# aasdasd.net
KiCad netlist of a schematic drawn in EAGLE
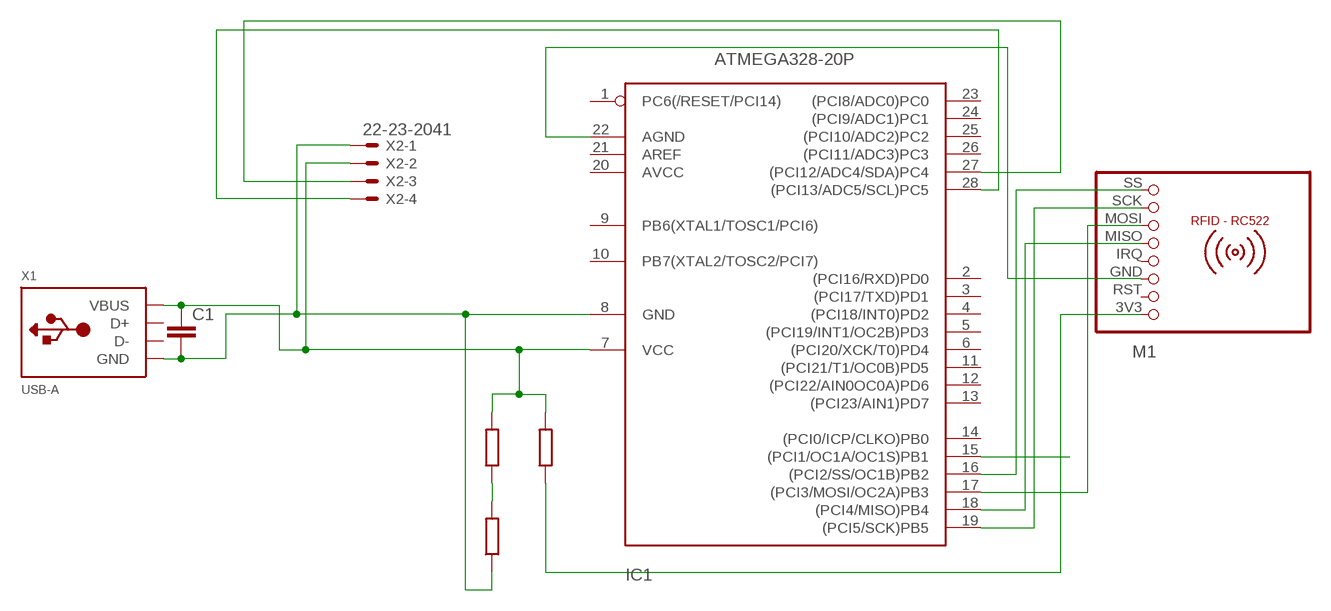
[diagram p0: schematic, sheet 1]

(export (version "E")
  (design (tool "Eeschema 10.0.6"))
  (components
    (comp (ref "C1")
      (value "C-EU025-050X050")
      (footprint "eagle-import:C025-050X050")
      (libsource (lib "eagle-import") (part "C-EU025-050X050"))
    )
    (comp (ref "IC1")
      (value "ATMEGA328-20P")
      (footprint "eagle-import:DIL28-3")
      (libsource (lib "eagle-import") (part "ATMEGA328P-20"))
    )
    (comp (ref "M1")
      (value "RFID-RC522")
      (footprint "eagle-import:RFID-RC522")
      (libsource (lib "eagle-import") (part "RFID-RC522"))
    )
    (comp (ref "X1")
      (value "USB-A")
      (footprint "eagle-import:MOLEX_480371000")
      (libsource (lib "eagle-import") (part "USB-A"))
    )
    (comp (ref "X2")
      (value "22-23-2041")
      (footprint "eagle-import:22-23-2041")
      (fields (field (name "MF") "MOLEX"))
      (libsource (lib "eagle-import") (part "22-23-2041"))
    )
  )
  (nets
    (net (code "1") (name "Net-(IC1-(PCI2{slash}SS{slash}OC1B)PB2)") (class "Default")
      (node (ref "IC1") (pin "16") (pinfunction "(PCI2/SS/OC1B)PB2_16") (pintype "bidirectional"))
      (node (ref "M1") (pin "SS") (pinfunction "8_SS") (pintype "passive"))
    )
    (net (code "2") (name "Net-(IC1-(PCI3{slash}MOSI{slash}OC2A)PB3)") (class "Default")
      (node (ref "IC1") (pin "17") (pinfunction "(PCI3/MOSI/OC2A)PB3_17") (pintype "bidirectional"))
      (node (ref "M1") (pin "MOSI") (pinfunction "6_MOSI") (pintype "passive"))
    )
    (net (code "3") (name "Net-(IC1-(PCI4{slash}MISO)PB4)") (class "Default")
      (node (ref "IC1") (pin "18") (pinfunction "(PCI4/MISO)PB4_18") (pintype "bidirectional"))
      (node (ref "M1") (pin "MISO") (pinfunction "5_MISO") (pintype "passive"))
    )
    (net (code "4") (name "Net-(IC1-(PCI5{slash}SCK)PB5)") (class "Default")
      (node (ref "IC1") (pin "19") (pinfunction "(PCI5/SCK)PB5_19") (pintype "bidirectional"))
      (node (ref "M1") (pin "SCK") (pinfunction "7_SCK") (pintype "passive"))
    )
    (net (code "5") (name "Net-(IC1-(PCI12{slash}ADC4{slash}SDA)PC4)") (class "Default")
      (node (ref "IC1") (pin "27") (pinfunction "(PCI12/ADC4/SDA)PC4_27") (pintype "bidirectional"))
      (node (ref "X2") (pin "3") (pinfunction "S_3") (pintype "passive"))
    )
    (net (code "6") (name "Net-(IC1-(PCI13{slash}ADC5{slash}SCL)PC5)") (class "Default")
      (node (ref "IC1") (pin "28") (pinfunction "(PCI13/ADC5/SCL)PC5_28") (pintype "bidirectional"))
      (node (ref "X2") (pin "4") (pinfunction "S_4") (pintype "passive"))
    )
    (net (code "7") (name "Net-(IC1-AGND)") (class "Default")
      (node (ref "IC1") (pin "22") (pinfunction "AGND_22") (pintype "bidirectional"))
      (node (ref "M1") (pin "GND") (pinfunction "3_GND") (pintype "passive"))
    )
    (net (code "8") (name "Net-(IC1-GND)") (class "Default")
      (node (ref "C1") (pin "2") (pinfunction "2_2") (pintype "passive"))
      (node (ref "IC1") (pin "8") (pinfunction "GND_8") (pintype "bidirectional"))
      (node (ref "X1") (pin "4") (pinfunction "GND_4") (pintype "power_in"))
      (node (ref "X2") (pin "1") (pinfunction "S_1") (pintype "passive"))
    )
    (net (code "9") (name "Net-(IC1-VCC)") (class "Default")
      (node (ref "C1") (pin "1") (pinfunction "1_1") (pintype "passive"))
      (node (ref "IC1") (pin "7") (pinfunction "VCC_7") (pintype "bidirectional"))
      (node (ref "X1") (pin "1") (pinfunction "VBUS_1") (pintype "power_in"))
      (node (ref "X2") (pin "2") (pinfunction "S_2") (pintype "passive"))
    )
    (net (code "10") (name "unconnected-(IC1-(PCI0{slash}ICP{slash}CLKO)PB0-Pad14)") (class "Default")
      (node (ref "IC1") (pin "14") (pinfunction "(PCI0/ICP/CLKO)PB0_14") (pintype "bidirectional"))
    )
    (net (code "11") (name "unconnected-(IC1-(PCI1{slash}OC1A{slash}OC1S)PB1-Pad15)") (class "Default")
      (node (ref "IC1") (pin "15") (pinfunction "(PCI1/OC1A/OC1S)PB1_15") (pintype "bidirectional"))
    )
    (net (code "12") (name "unconnected-(IC1-(PCI8{slash}ADC0)PC0-Pad23)") (class "Default")
      (node (ref "IC1") (pin "23") (pinfunction "(PCI8/ADC0)PC0_23") (pintype "bidirectional"))
    )
    (net (code "13") (name "unconnected-(IC1-(PCI9{slash}ADC1)PC1-Pad24)") (class "Default")
      (node (ref "IC1") (pin "24") (pinfunction "(PCI9/ADC1)PC1_24") (pintype "bidirectional"))
    )
    (net (code "14") (name "unconnected-(IC1-(PCI10{slash}ADC2)PC2-Pad25)") (class "Default")
      (node (ref "IC1") (pin "25") (pinfunction "(PCI10/ADC2)PC2_25") (pintype "bidirectional"))
    )
    (net (code "15") (name "unconnected-(IC1-(PCI11{slash}ADC3)PC3-Pad26)") (class "Default")
      (node (ref "IC1") (pin "26") (pinfunction "(PCI11/ADC3)PC3_26") (pintype "bidirectional"))
    )
    (net (code "16") (name "unconnected-(IC1-(PCI16{slash}RXD)PD0-Pad2)") (class "Default")
      (node (ref "IC1") (pin "2") (pinfunction "(PCI16/RXD)PD0_2") (pintype "bidirectional"))
    )
    (net (code "17") (name "unconnected-(IC1-(PCI17{slash}TXD)PD1-Pad3)") (class "Default")
      (node (ref "IC1") (pin "3") (pinfunction "(PCI17/TXD)PD1_3") (pintype "bidirectional"))
    )
    (net (code "18") (name "unconnected-(IC1-(PCI18{slash}INT0)PD2-Pad4)") (class "Default")
      (node (ref "IC1") (pin "4") (pinfunction "(PCI18/INT0)PD2_4") (pintype "bidirectional"))
    )
    (net (code "19") (name "unconnected-(IC1-(PCI19{slash}INT1{slash}OC2B)PD3-Pad5)") (class "Default")
      (node (ref "IC1") (pin "5") (pinfunction "(PCI19/INT1/OC2B)PD3_5") (pintype "bidirectional"))
    )
    (net (code "20") (name "unconnected-(IC1-(PCI20{slash}XCK{slash}T0)PD4-Pad6)") (class "Default")
      (node (ref "IC1") (pin "6") (pinfunction "(PCI20/XCK/T0)PD4_6") (pintype "bidirectional"))
    )
    (net (code "21") (name "unconnected-(IC1-(PCI21{slash}T1{slash}OC0B)PD5-Pad11)") (class "Default")
      (node (ref "IC1") (pin "11") (pinfunction "(PCI21/T1/OC0B)PD5_11") (pintype "bidirectional"))
    )
    (net (code "22") (name "unconnected-(IC1-(PCI22{slash}AIN0OC0A)PD6-Pad12)") (class "Default")
      (node (ref "IC1") (pin "12") (pinfunction "(PCI22/AIN0OC0A)PD6_12") (pintype "bidirectional"))
    )
    (net (code "23") (name "unconnected-(IC1-(PCI23{slash}AIN1)PD7-Pad13)") (class "Default")
      (node (ref "IC1") (pin "13") (pinfunction "(PCI23/AIN1)PD7_13") (pintype "bidirectional"))
    )
    (net (code "24") (name "unconnected-(IC1-AREF-Pad21)") (class "Default")
      (node (ref "IC1") (pin "21") (pinfunction "AREF_21") (pintype "bidirectional"))
    )
    (net (code "25") (name "unconnected-(IC1-AVCC-Pad20)") (class "Default")
      (node (ref "IC1") (pin "20") (pinfunction "AVCC_20") (pintype "bidirectional"))
    )
    (net (code "26") (name "unconnected-(IC1-PB6(XTAL1{slash}TOSC1{slash}PCI6)-Pad9)") (class "Default")
      (node (ref "IC1") (pin "9") (pinfunction "PB6(XTAL1/TOSC1/PCI6)_9") (pintype "bidirectional"))
    )
    (net (code "27") (name "unconnected-(IC1-PB7(XTAL2{slash}TOSC2{slash}PCI7)-Pad10)") (class "Default")
      (node (ref "IC1") (pin "10") (pinfunction "PB7(XTAL2/TOSC2/PCI7)_10") (pintype "bidirectional"))
    )
    (net (code "28") (name "unconnected-(IC1-PC6({slash}RESET{slash}PCI14)-Pad1)") (class "Default")
      (node (ref "IC1") (pin "1") (pinfunction "PC6(/RESET/PCI14)_1") (pintype "bidirectional"))
    )
    (net (code "29") (name "unconnected-(M1-1-Pad3V3)") (class "Default")
      (node (ref "M1") (pin "3V3") (pinfunction "1_3V3") (pintype "passive"))
    )
    (net (code "30") (name "unconnected-(M1-2-PadRST)") (class "Default")
      (node (ref "M1") (pin "RST") (pinfunction "2_RST") (pintype "passive"))
    )
    (net (code "31") (name "unconnected-(M1-4-PadIRQ)") (class "Default")
      (node (ref "M1") (pin "IRQ") (pinfunction "4_IRQ") (pintype "passive"))
    )
    (net (code "32") (name "unconnected-(X1-D+-Pad3)") (class "Default")
      (node (ref "X1") (pin "3") (pinfunction "D+_3") (pintype "bidirectional"))
    )
    (net (code "33") (name "unconnected-(X1-D--Pad2)") (class "Default")
      (node (ref "X1") (pin "2") (pinfunction "D-_2") (pintype "bidirectional"))
    )
  )
)
